# Bandpass.net
KiCad netlist of a schematic drawn in Altium Designer
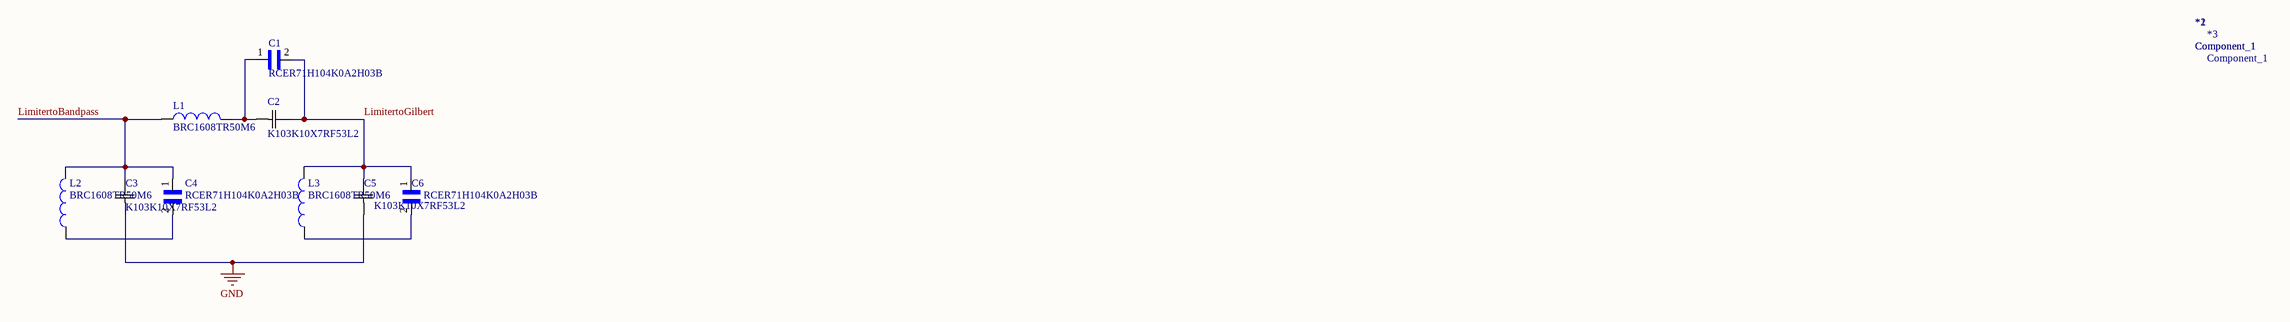
[diagram p0: Bandpass.SchDoc]

(export (version "E")
  (design (tool "Eeschema 10.0.6"))
  (components
    (comp (ref "*1") (value "Component_1") (libsource (lib "PRPC004SAAN-RC") (part "Component_1")))
    (comp (ref "*2") (value "Component_1") (libsource (lib "PRPC004SAAN-RC") (part "Component_1")))
    (comp (ref "*3") (value "Component_1") (libsource (lib "PRPC004SAAN-RC") (part "Component_1")))
    (comp (ref "C1")
      (value "RCER71H104K0A2H03B")
      (footprint "CAP_RCER71H104K0A2H03B")
      (description "Cap Ceramic 1pF 50V C0G 0.25pF Radial 2.5mm 125C Automotive Bulk")
      (libsource (lib "") (part "RCER71H104K0A2H03B_1"))
    )
    (comp (ref "C2")
      (value "K103K10X7RF53L2")
      (footprint "K103K10X7RF53L2_VIS")
      (description "No Description Available")
      (libsource (lib "K103K10X7RF53L2") (part "K103K10X7RF53L2"))
    )
    (comp (ref "C3")
      (value "K103K10X7RF53L2")
      (footprint "K103K10X7RF53L2_VIS")
      (description "No Description Available")
      (libsource (lib "K103K10X7RF53L2") (part "K103K10X7RF53L2"))
    )
    (comp (ref "C4")
      (value "RCER71H104K0A2H03B")
      (footprint "CAP_RCER71H104K0A2H03B")
      (description "Cap Ceramic 1pF 50V C0G 0.25pF Radial 2.5mm 125C Automotive Bulk")
      (libsource (lib "RCER71H104K0A2H03B") (part "RCER71H104K0A2H03B"))
    )
    (comp (ref "C5")
      (value "K103K10X7RF53L2")
      (footprint "K103K10X7RF53L2_VIS")
      (description "No Description Available")
      (libsource (lib "K103K10X7RF53L2") (part "K103K10X7RF53L2"))
    )
    (comp (ref "C6")
      (value "RCER71H104K0A2H03B")
      (footprint "CAP_RCER71H104K0A2H03B")
      (description "Cap Ceramic 1pF 50V C0G 0.25pF Radial 2.5mm 125C Automotive Bulk")
      (libsource (lib "RCER71H104K0A2H03B") (part "RCER71H104K0A2H03B"))
    )
    (comp (ref "L1")
      (value "BRC1608TR50M6")
      (footprint "INDC1608X100N")
      (description "Inductor Power Chip Wirewound 500nH 20% 6MHz Ferrite 1.05A 117mOhm DCR 0603 T/R")
      (libsource (lib "BRC1608TR50M6") (part "BRC1608TR50M6"))
    )
    (comp (ref "L2")
      (value "BRC1608TR50M6")
      (footprint "INDC1608X100N")
      (description "Inductor Power Chip Wirewound 500nH 20% 6MHz Ferrite 1.05A 117mOhm DCR 0603 T/R")
      (libsource (lib "BRC1608TR50M6") (part "BRC1608TR50M6"))
    )
    (comp (ref "L3")
      (value "BRC1608TR50M6")
      (footprint "INDC1608X100N")
      (description "Inductor Power Chip Wirewound 500nH 20% 6MHz Ferrite 1.05A 117mOhm DCR 0603 T/R")
      (libsource (lib "BRC1608TR50M6") (part "BRC1608TR50M6"))
    )
  )
  (nets
    (net (code "1") (name "/LimitertoBandpass") (class "Default")
      (node (ref "C3") (pin "2") (pinfunction "2_2") (pintype "passive"))
      (node (ref "C4") (pin "1") (pinfunction "1_1") (pintype "passive"))
      (node (ref "L1") (pin "1") (pinfunction "1_1") (pintype "passive"))
      (node (ref "L2") (pin "2") (pinfunction "2_2") (pintype "passive"))
    )
    (net (code "2") (name "/LimitertoGilbert") (class "Default")
      (node (ref "C1") (pin "2") (pinfunction "2_2") (pintype "passive"))
      (node (ref "C2") (pin "2") (pinfunction "2_2") (pintype "passive"))
      (node (ref "C5") (pin "2") (pinfunction "2_2") (pintype "passive"))
      (node (ref "C6") (pin "1") (pinfunction "1_1") (pintype "passive"))
      (node (ref "L3") (pin "2") (pinfunction "2_2") (pintype "passive"))
    )
    (net (code "3") (name "GND") (class "Default")
      (node (ref "C3") (pin "1") (pinfunction "1_1") (pintype "passive"))
      (node (ref "C5") (pin "1") (pinfunction "1_1") (pintype "passive"))
    )
    (net (code "4") (name "Net-(C1-Pad1)") (class "Default")
      (node (ref "C1") (pin "1") (pinfunction "1_1") (pintype "passive"))
      (node (ref "C2") (pin "1") (pinfunction "1_1") (pintype "passive"))
      (node (ref "L1") (pin "2") (pinfunction "2_2") (pintype "passive"))
    )
    (net (code "5") (name "Net-(C4-Pad2)") (class "Default")
      (node (ref "C4") (pin "2") (pinfunction "2_2") (pintype "passive"))
      (node (ref "L2") (pin "1") (pinfunction "1_1") (pintype "passive"))
    )
    (net (code "6") (name "Net-(C6-Pad2)") (class "Default")
      (node (ref "C6") (pin "2") (pinfunction "2_2") (pintype "passive"))
      (node (ref "L3") (pin "1") (pinfunction "1_1") (pintype "passive"))
    )
  )
)
